# SOLDERING_STATION.net
KiCad netlist of a schematic drawn in EAGLE
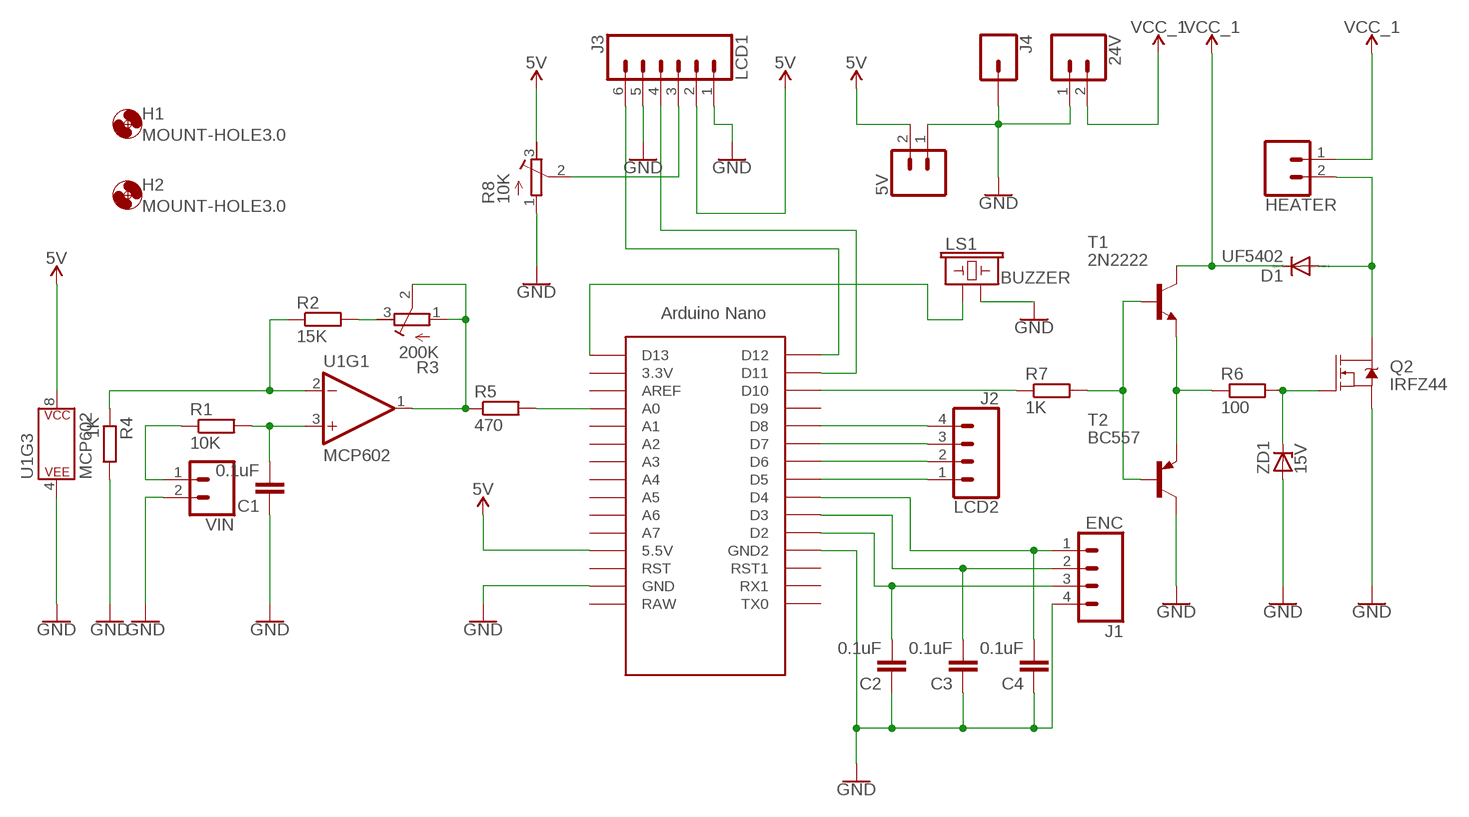
[diagram p0: schematic, sheet 1]

(export (version "E")
  (design (tool "Eeschema 10.0.6"))
  (components
    (comp (ref "5V")
      (value "CONN_025MM")
      (footprint "eagle-import:SCREWTERMINAL-5MM-2")
      (libsource (lib "eagle-import") (part "CONN_025MM"))
    )
    (comp (ref "24V")
      (value "CONN_025MM")
      (footprint "eagle-import:SCREWTERMINAL-5MM-2")
      (libsource (lib "eagle-import") (part "CONN_025MM"))
    )
    (comp (ref "C1")
      (value "0.1uF")
      (footprint "eagle-import:C025-024X044")
      (libsource (lib "eagle-import") (part "C-EU025-024X044"))
    )
    (comp (ref "C2")
      (value "0.1uF")
      (footprint "eagle-import:C025-024X044")
      (libsource (lib "eagle-import") (part "C-EU025-024X044"))
    )
    (comp (ref "C3")
      (value "0.1uF")
      (footprint "eagle-import:C025-024X044")
      (libsource (lib "eagle-import") (part "C-EU025-024X044"))
    )
    (comp (ref "C4")
      (value "0.1uF")
      (footprint "eagle-import:C025-024X044")
      (libsource (lib "eagle-import") (part "C-EU025-024X044"))
    )
    (comp (ref "D1")
      (value "UF5402")
      (footprint "eagle-import:DO41-10")
      (libsource (lib "eagle-import") (part "UF4003"))
    )
    (comp (ref "H1")
      (value "MOUNT-HOLE3.0")
      (footprint "eagle-import:3,0")
      (libsource (lib "eagle-import") (part "MOUNT-HOLE3.0"))
    )
    (comp (ref "H2")
      (value "MOUNT-HOLE3.0")
      (footprint "eagle-import:3,0")
      (libsource (lib "eagle-import") (part "MOUNT-HOLE3.0"))
    )
    (comp (ref "HEATER")
      (value "CONN_02PTH4")
      (footprint "eagle-import:1X02_XTRA_BIG")
      (libsource (lib "eagle-import") (part "CONN_02PTH4"))
    )
    (comp (ref "J1")
      (value "ENC")
      (footprint "eagle-import:1X04_LONGPADS")
      (libsource (lib "eagle-import") (part "CONN_04LONGPADS"))
    )
    (comp (ref "J2")
      (value "LCD2")
      (footprint "eagle-import:1X04_LONGPADS")
      (libsource (lib "eagle-import") (part "CONN_04LONGPADS"))
    )
    (comp (ref "J3")
      (value "LCD1")
      (footprint "eagle-import:1X06_LONGPADS")
      (libsource (lib "eagle-import") (part "CONN_06LONGPADS"))
    )
    (comp (ref "J4")
      (value "CONN_01PTH_2MM")
      (footprint "eagle-import:1X01_2MM")
      (libsource (lib "eagle-import") (part "CONN_01PTH_2MM"))
    )
    (comp (ref "LS1")
      (value "BUZZER")
      (footprint "eagle-import:BUZZER-12MM-NS")
      (libsource (lib "eagle-import") (part "BUZZER-PTH_NO_SILK"))
    )
    (comp (ref "Q2")
      (value "IRFZ44")
      (footprint "eagle-import:TO220V")
      (libsource (lib "eagle-import") (part "MOSFET-NCH-FQP30N06L"))
    )
    (comp (ref "R1")
      (value "10K")
      (footprint "eagle-import:0204_7")
      (libsource (lib "eagle-import") (part "R-EU_0204/7"))
    )
    (comp (ref "R2")
      (value "15K")
      (footprint "eagle-import:0204_7")
      (libsource (lib "eagle-import") (part "R-EU_0204/7"))
    )
    (comp (ref "R3")
      (value "200K")
      (footprint "eagle-import:RTRIM64W")
      (libsource (lib "eagle-import") (part "R-TRIMM64W"))
    )
    (comp (ref "R4")
      (value "1K")
      (footprint "eagle-import:0204_7")
      (libsource (lib "eagle-import") (part "R-EU_0204/7"))
    )
    (comp (ref "R5")
      (value "470")
      (footprint "eagle-import:0204_7")
      (libsource (lib "eagle-import") (part "R-EU_0204/7"))
    )
    (comp (ref "R6")
      (value "100")
      (footprint "eagle-import:0204_7")
      (libsource (lib "eagle-import") (part "R-EU_0204/7"))
    )
    (comp (ref "R7")
      (value "1K")
      (footprint "eagle-import:0204_7")
      (libsource (lib "eagle-import") (part "R-EU_0204/7"))
    )
    (comp (ref "R8")
      (value "10K")
      (footprint "eagle-import:RTRIM64W")
      (libsource (lib "eagle-import") (part "R-TRIMM64W"))
    )
    (comp (ref "T1")
      (value "2N2222")
      (footprint "eagle-import:TO92-EBC-OVAL")
      (libsource (lib "eagle-import") (part "2N2222"))
    )
    (comp (ref "T2")
      (value "BC557")
      (footprint "eagle-import:TO92")
      (libsource (lib "eagle-import") (part "BC557"))
    )
    (comp (ref "U$1")
      (value "NANO")
      (footprint "eagle-import:NANO")
      (libsource (lib "eagle-import") (part "NANO"))
    )
    (comp (ref "U1")
      (value "MCP602")
      (footprint "eagle-import:DIP08")
      (libsource (lib "eagle-import") (part "LM358"))
    )
    (comp (ref "VIN")
      (value "CONN_02POLAR_LOCK")
      (footprint "eagle-import:MOLEX-1X2_LOCK")
      (libsource (lib "eagle-import") (part "CONN_02POLAR_LOCK"))
    )
    (comp (ref "ZD1")
      (value "15V")
      (footprint "eagle-import:DO41Z10")
      (libsource (lib "eagle-import") (part "1N4728"))
    )
  )
  (nets
    (net (code "1") (name "5V") (class "Default")
      (node (ref "5V") (pin "2") (pinfunction "2_2") (pintype "passive"))
      (node (ref "J3") (pin "2") (pinfunction "2_2") (pintype "passive"))
      (node (ref "R8") (pin "3") (pinfunction "E_3") (pintype "passive"))
      (node (ref "U$1") (pin "5V") (pinfunction "5.5V_5V") (pintype "bidirectional"))
      (node (ref "U1") (pin "8") (pinfunction "P$V+_8") (pintype "bidirectional"))
    )
    (net (code "2") (name "GND") (class "Default")
      (node (ref "24V") (pin "1") (pinfunction "1_1") (pintype "passive"))
      (node (ref "5V") (pin "1") (pinfunction "1_1") (pintype "passive"))
      (node (ref "C1") (pin "1") (pinfunction "1_1") (pintype "passive"))
      (node (ref "C2") (pin "1") (pinfunction "1_1") (pintype "passive"))
      (node (ref "C3") (pin "1") (pinfunction "1_1") (pintype "passive"))
      (node (ref "C4") (pin "1") (pinfunction "1_1") (pintype "passive"))
      (node (ref "J1") (pin "4") (pinfunction "4_4") (pintype "passive"))
      (node (ref "J3") (pin "1") (pinfunction "1_1") (pintype "passive"))
      (node (ref "J3") (pin "5") (pinfunction "5_5") (pintype "passive"))
      (node (ref "J4") (pin "1") (pinfunction "1_1") (pintype "passive"))
      (node (ref "LS1") (pin "-") (pinfunction "2_-") (pintype "passive"))
      (node (ref "Q2") (pin "3") (pinfunction "S_3") (pintype "bidirectional"))
      (node (ref "R4") (pin "2") (pinfunction "2_2") (pintype "passive"))
      (node (ref "R8") (pin "1") (pinfunction "A_1") (pintype "passive"))
      (node (ref "T2") (pin "3") (pinfunction "C_3") (pintype "passive"))
      (node (ref "U$1") (pin "GND") (pinfunction "GND_GND") (pintype "bidirectional"))
      (node (ref "U$1") (pin "GND1") (pinfunction "GND2_GND1") (pintype "bidirectional"))
      (node (ref "U1") (pin "4") (pinfunction "P$V-_4") (pintype "bidirectional"))
      (node (ref "VIN") (pin "2") (pinfunction "2_2") (pintype "passive"))
      (node (ref "ZD1") (pin "A") (pinfunction "A_A") (pintype "passive"))
    )
    (net (code "3") (name "Net-(C2-Pad2)") (class "Default")
      (node (ref "C2") (pin "2") (pinfunction "2_2") (pintype "passive"))
      (node (ref "J1") (pin "3") (pinfunction "3_3") (pintype "passive"))
      (node (ref "U$1") (pin "D2") (pinfunction "D2_D2") (pintype "bidirectional"))
    )
    (net (code "4") (name "Net-(C3-Pad2)") (class "Default")
      (node (ref "C3") (pin "2") (pinfunction "2_2") (pintype "passive"))
      (node (ref "J1") (pin "2") (pinfunction "2_2") (pintype "passive"))
      (node (ref "U$1") (pin "D3") (pinfunction "D3_D3") (pintype "bidirectional"))
    )
    (net (code "5") (name "Net-(C4-Pad2)") (class "Default")
      (node (ref "C4") (pin "2") (pinfunction "2_2") (pintype "passive"))
      (node (ref "J1") (pin "1") (pinfunction "1_1") (pintype "passive"))
      (node (ref "U$1") (pin "D4") (pinfunction "D4_D4") (pintype "bidirectional"))
    )
    (net (code "6") (name "Net-(J2-Pad1)") (class "Default")
      (node (ref "J2") (pin "1") (pinfunction "1_1") (pintype "passive"))
      (node (ref "U$1") (pin "D5") (pinfunction "D5_D5") (pintype "bidirectional"))
    )
    (net (code "7") (name "Net-(J2-Pad2)") (class "Default")
      (node (ref "J2") (pin "2") (pinfunction "2_2") (pintype "passive"))
      (node (ref "U$1") (pin "D6") (pinfunction "D6_D6") (pintype "bidirectional"))
    )
    (net (code "8") (name "Net-(J2-Pad3)") (class "Default")
      (node (ref "J2") (pin "3") (pinfunction "3_3") (pintype "passive"))
      (node (ref "U$1") (pin "D7") (pinfunction "D7_D7") (pintype "bidirectional"))
    )
    (net (code "9") (name "Net-(J2-Pad4)") (class "Default")
      (node (ref "J2") (pin "4") (pinfunction "4_4") (pintype "passive"))
      (node (ref "U$1") (pin "D8") (pinfunction "D8_D8") (pintype "bidirectional"))
    )
    (net (code "10") (name "Net-(J3-Pad4)") (class "Default")
      (node (ref "J3") (pin "4") (pinfunction "4_4") (pintype "passive"))
      (node (ref "U$1") (pin "D11") (pinfunction "D11_D11") (pintype "bidirectional"))
    )
    (net (code "11") (name "Net-(J3-Pad6)") (class "Default")
      (node (ref "J3") (pin "6") (pinfunction "6_6") (pintype "passive"))
      (node (ref "U$1") (pin "D12") (pinfunction "D12_D12") (pintype "bidirectional"))
    )
    (net (code "12") (name "Net-(LS1-1)") (class "Default")
      (node (ref "LS1") (pin "+") (pinfunction "1_+") (pintype "passive"))
      (node (ref "U$1") (pin "D13") (pinfunction "D13_D13") (pintype "bidirectional"))
    )
    (net (code "13") (name "Net-(Q2-D)") (class "Default")
      (node (ref "D1") (pin "A") (pinfunction "A_A") (pintype "passive"))
      (node (ref "HEATER") (pin "2") (pinfunction "2_2") (pintype "passive"))
      (node (ref "Q2") (pin "2") (pinfunction "D_2") (pintype "bidirectional"))
    )
    (net (code "14") (name "Net-(Q2-G)") (class "Default")
      (node (ref "Q2") (pin "1") (pinfunction "G_1") (pintype "bidirectional"))
      (node (ref "R6") (pin "2") (pinfunction "2_2") (pintype "passive"))
      (node (ref "ZD1") (pin "C") (pinfunction "C_C") (pintype "passive"))
    )
    (net (code "15") (name "Net-(R1-Pad1)") (class "Default")
      (node (ref "R1") (pin "1") (pinfunction "1_1") (pintype "passive"))
      (node (ref "VIN") (pin "1") (pinfunction "1_1") (pintype "passive"))
    )
    (net (code "16") (name "Net-(R3-A)") (class "Default")
      (node (ref "R3") (pin "1") (pinfunction "A_1") (pintype "passive"))
      (node (ref "R3") (pin "2") (pinfunction "S_2") (pintype "passive"))
      (node (ref "R5") (pin "1") (pinfunction "1_1") (pintype "passive"))
      (node (ref "U1") (pin "1") (pinfunction "OUT_1") (pintype "output"))
    )
    (net (code "17") (name "Net-(R3-E)") (class "Default")
      (node (ref "R2") (pin "2") (pinfunction "2_2") (pintype "passive"))
      (node (ref "R3") (pin "3") (pinfunction "E_3") (pintype "passive"))
    )
    (net (code "18") (name "Net-(R5-Pad2)") (class "Default")
      (node (ref "R5") (pin "2") (pinfunction "2_2") (pintype "passive"))
      (node (ref "U$1") (pin "A0") (pinfunction "A0_A0") (pintype "bidirectional"))
    )
    (net (code "19") (name "Net-(R7-Pad1)") (class "Default")
      (node (ref "R7") (pin "1") (pinfunction "1_1") (pintype "passive"))
      (node (ref "U$1") (pin "D10") (pinfunction "D10_D10") (pintype "bidirectional"))
    )
    (net (code "20") (name "Net-(R8-S)") (class "Default")
      (node (ref "J3") (pin "3") (pinfunction "3_3") (pintype "passive"))
      (node (ref "R8") (pin "2") (pinfunction "S_2") (pintype "passive"))
    )
    (net (code "21") (name "Net-(T2-B)") (class "Default")
      (node (ref "R7") (pin "2") (pinfunction "2_2") (pintype "passive"))
      (node (ref "T1") (pin "B") (pinfunction "B_B") (pintype "passive"))
      (node (ref "T2") (pin "2") (pinfunction "B_2") (pintype "passive"))
    )
    (net (code "22") (name "Net-(T2-E)") (class "Default")
      (node (ref "R6") (pin "1") (pinfunction "1_1") (pintype "passive"))
      (node (ref "T1") (pin "E") (pinfunction "E_E") (pintype "passive"))
      (node (ref "T2") (pin "1") (pinfunction "E_1") (pintype "passive"))
    )
    (net (code "23") (name "Net-(U1A-+IN)") (class "Default")
      (node (ref "C1") (pin "2") (pinfunction "2_2") (pintype "passive"))
      (node (ref "R1") (pin "2") (pinfunction "2_2") (pintype "passive"))
      (node (ref "U1") (pin "3") (pinfunction "+IN_3") (pintype "input"))
    )
    (net (code "24") (name "Net-(U1A--IN)") (class "Default")
      (node (ref "R2") (pin "1") (pinfunction "1_1") (pintype "passive"))
      (node (ref "R4") (pin "1") (pinfunction "1_1") (pintype "passive"))
      (node (ref "U1") (pin "2") (pinfunction "-IN_2") (pintype "input"))
    )
    (net (code "25") (name "VCC_1") (class "Default")
      (node (ref "24V") (pin "2") (pinfunction "2_2") (pintype "passive"))
      (node (ref "D1") (pin "C") (pinfunction "C_C") (pintype "passive"))
      (node (ref "HEATER") (pin "1") (pinfunction "1_1") (pintype "passive"))
      (node (ref "T1") (pin "C") (pinfunction "C_C") (pintype "passive"))
    )
    (net (code "26") (name "unconnected-(U$1-Pad3.3V)") (class "Default")
      (node (ref "U$1") (pin "3.3V") (pinfunction "3.3V_3.3V") (pintype "bidirectional"))
    )
    (net (code "27") (name "unconnected-(U$1-PadA1)") (class "Default")
      (node (ref "U$1") (pin "A1") (pinfunction "A1_A1") (pintype "bidirectional"))
    )
    (net (code "28") (name "unconnected-(U$1-PadA2)") (class "Default")
      (node (ref "U$1") (pin "A2") (pinfunction "A2_A2") (pintype "bidirectional"))
    )
    (net (code "29") (name "unconnected-(U$1-PadA3)") (class "Default")
      (node (ref "U$1") (pin "A3") (pinfunction "A3_A3") (pintype "bidirectional"))
    )
    (net (code "30") (name "unconnected-(U$1-PadA4)") (class "Default")
      (node (ref "U$1") (pin "A4") (pinfunction "A4_A4") (pintype "bidirectional"))
    )
    (net (code "31") (name "unconnected-(U$1-PadA5)") (class "Default")
      (node (ref "U$1") (pin "A5") (pinfunction "A5_A5") (pintype "bidirectional"))
    )
    (net (code "32") (name "unconnected-(U$1-PadA6)") (class "Default")
      (node (ref "U$1") (pin "A6") (pinfunction "A6_A6") (pintype "bidirectional"))
    )
    (net (code "33") (name "unconnected-(U$1-PadA7)") (class "Default")
      (node (ref "U$1") (pin "A7") (pinfunction "A7_A7") (pintype "bidirectional"))
    )
    (net (code "34") (name "unconnected-(U$1-PadAREF)") (class "Default")
      (node (ref "U$1") (pin "AREF") (pinfunction "AREF_AREF") (pintype "bidirectional"))
    )
    (net (code "35") (name "unconnected-(U$1-PadD9)") (class "Default")
      (node (ref "U$1") (pin "D9") (pinfunction "D9_D9") (pintype "bidirectional"))
    )
    (net (code "36") (name "unconnected-(U$1-PadICSP1)") (class "Default")
      (node (ref "U$1") (pin "ICSP1") (pinfunction "ICSP1_ICSP1") (pintype "bidirectional"))
    )
    (net (code "37") (name "unconnected-(U$1-PadICSP2)") (class "Default")
      (node (ref "U$1") (pin "ICSP2") (pinfunction "ICSP2_ICSP2") (pintype "bidirectional"))
    )
    (net (code "38") (name "unconnected-(U$1-PadICSP3)") (class "Default")
      (node (ref "U$1") (pin "ICSP3") (pinfunction "ICSP3_ICSP3") (pintype "bidirectional"))
    )
    (net (code "39") (name "unconnected-(U$1-PadICSP4)") (class "Default")
      (node (ref "U$1") (pin "ICSP4") (pinfunction "ICSP4_ICSP4") (pintype "bidirectional"))
    )
    (net (code "40") (name "unconnected-(U$1-PadICSP5)") (class "Default")
      (node (ref "U$1") (pin "ICSP5") (pinfunction "ICSP5_ICSP5") (pintype "bidirectional"))
    )
    (net (code "41") (name "unconnected-(U$1-PadICSP6)") (class "Default")
      (node (ref "U$1") (pin "ICSP6") (pinfunction "ICSP6_ICSP6") (pintype "bidirectional"))
    )
    (net (code "42") (name "unconnected-(U$1-PadRAW)") (class "Default")
      (node (ref "U$1") (pin "RAW") (pinfunction "RAW_RAW") (pintype "bidirectional"))
    )
    (net (code "43") (name "unconnected-(U$1-PadRST)") (class "Default")
      (node (ref "U$1") (pin "RST") (pinfunction "RST_RST") (pintype "bidirectional"))
    )
    (net (code "44") (name "unconnected-(U$1-PadRST1)") (class "Default")
      (node (ref "U$1") (pin "RST1") (pinfunction "RST1_RST1") (pintype "bidirectional"))
    )
    (net (code "45") (name "unconnected-(U$1-PadRX1)") (class "Default")
      (node (ref "U$1") (pin "RX1") (pinfunction "RX1_RX1") (pintype "bidirectional"))
    )
    (net (code "46") (name "unconnected-(U$1-PadTX0)") (class "Default")
      (node (ref "U$1") (pin "TX0") (pinfunction "TX0_TX0") (pintype "bidirectional"))
    )
  )
)
